# MidDout.net
KiCad netlist of a schematic drawn in Altium Designer
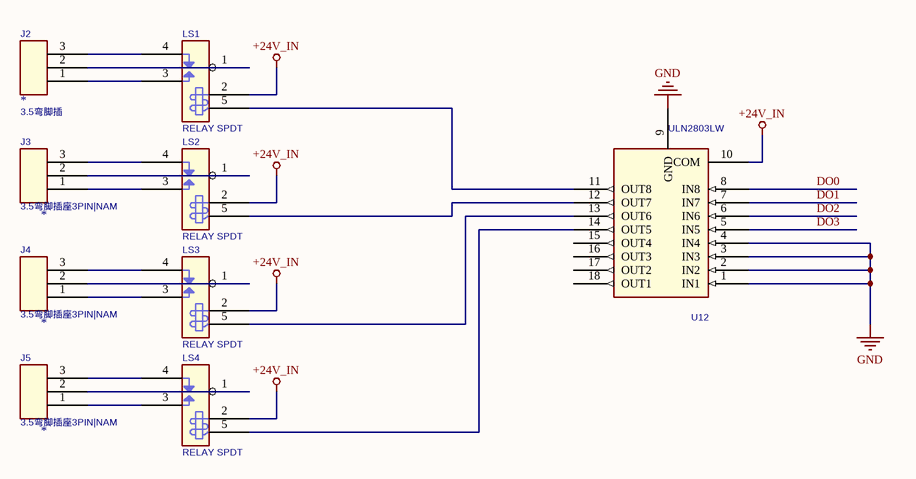
[diagram p0: MidDout.SchDoc]

(export (version "E")
  (design (tool "Eeschema 10.0.6"))
  (components
    (comp (ref "J2")
      (value "*")
      (footprint "3.5-P3")
      (fields (field (name "ALTIUM_UNNAMED_1") "3.5Íä½Å²å"))
      (libsource (lib "*") (part "CON3"))
    )
    (comp (ref "J3")
      (value "*")
      (footprint "3.5-P3")
      (fields (field (name "ALTIUM_UNNAMED_1") "3.5Íä½Å²å×ù3PIN"))
      (libsource (lib "*") (part "CON3"))
    )
    (comp (ref "J4")
      (value "*")
      (footprint "3.5-P3")
      (fields (field (name "ALTIUM_UNNAMED_1") "3.5Íä½Å²å×ù3PIN"))
      (libsource (lib "*") (part "CON3"))
    )
    (comp (ref "J5")
      (value "*")
      (footprint "3.5-P3")
      (fields (field (name "ALTIUM_UNNAMED_1") "3.5Íä½Å²å×ù3PIN"))
      (libsource (lib "*") (part "CON3"))
    )
    (comp (ref "LS1")
      (value "RELAY SPDT")
      (footprint "RELAY_OMRON_G5LE-14")
      (libsource (lib "*") (part "RELAY SPDT_1"))
    )
    (comp (ref "LS2")
      (value "RELAY SPDT")
      (footprint "RELAY_OMRON_G5LE-14")
      (libsource (lib "*") (part "RELAY SPDT_1"))
    )
    (comp (ref "LS3")
      (value "RELAY SPDT")
      (footprint "RELAY_OMRON_G5LE-14")
      (libsource (lib "*") (part "RELAY SPDT_1"))
    )
    (comp (ref "LS4")
      (value "RELAY SPDT")
      (footprint "RELAY_OMRON_G5LE-14")
      (libsource (lib "*") (part "RELAY SPDT_1"))
    )
    (comp (ref "U12") (value "ULN2803LW") (footprint "SO18WN") (libsource (lib "*") (part "ULN2803")))
  )
  (nets
    (net (code "1") (name "+24V_IN") (class "Default")
      (node (ref "LS1") (pin "2") (pinfunction "COIL2_2") (pintype "passive"))
      (node (ref "LS2") (pin "2") (pinfunction "COIL2_2") (pintype "passive"))
      (node (ref "LS3") (pin "2") (pinfunction "COIL2_2") (pintype "passive"))
      (node (ref "LS4") (pin "2") (pinfunction "COIL2_2") (pintype "passive"))
      (node (ref "U12") (pin "10") (pinfunction "COM_10") (pintype "passive"))
    )
    (net (code "2") (name "/DO0") (class "Default")
      (node (ref "U12") (pin "8") (pinfunction "IN8_8") (pintype "input"))
    )
    (net (code "3") (name "/DO1") (class "Default")
      (node (ref "U12") (pin "7") (pinfunction "IN7_7") (pintype "input"))
    )
    (net (code "4") (name "/DO2") (class "Default")
      (node (ref "U12") (pin "6") (pinfunction "IN6_6") (pintype "input"))
    )
    (net (code "5") (name "/DO3") (class "Default")
      (node (ref "U12") (pin "5") (pinfunction "IN5_5") (pintype "input"))
    )
    (net (code "6") (name "GND") (class "Default")
      (node (ref "U12") (pin "1") (pinfunction "IN1_1") (pintype "input"))
      (node (ref "U12") (pin "2") (pinfunction "IN2_2") (pintype "input"))
      (node (ref "U12") (pin "3") (pinfunction "IN3_3") (pintype "input"))
      (node (ref "U12") (pin "4") (pinfunction "IN4_4") (pintype "input"))
      (node (ref "U12") (pin "9") (pinfunction "GND_9") (pintype "power_in"))
    )
    (net (code "7") (name "Net-(LS1-COIL1)") (class "Default")
      (node (ref "LS1") (pin "5") (pinfunction "COIL1_5") (pintype "passive"))
      (node (ref "U12") (pin "11") (pinfunction "OUT8_11") (pintype "output"))
    )
    (net (code "8") (name "Net-(LS1-COMMON)") (class "Default")
      (node (ref "J2") (pin "2") (pinfunction "2_2") (pintype "passive"))
      (node (ref "LS1") (pin "1") (pinfunction "COMMON_1") (pintype "passive"))
    )
    (net (code "9") (name "Net-(LS1-NC)") (class "Default")
      (node (ref "J2") (pin "3") (pinfunction "3_3") (pintype "passive"))
      (node (ref "LS1") (pin "4") (pinfunction "NC_4") (pintype "passive"))
    )
    (net (code "10") (name "Net-(LS1-NO)") (class "Default")
      (node (ref "J2") (pin "1") (pinfunction "1_1") (pintype "passive"))
      (node (ref "LS1") (pin "3") (pinfunction "NO_3") (pintype "passive"))
    )
    (net (code "11") (name "Net-(LS2-COIL1)") (class "Default")
      (node (ref "LS2") (pin "5") (pinfunction "COIL1_5") (pintype "passive"))
      (node (ref "U12") (pin "12") (pinfunction "OUT7_12") (pintype "output"))
    )
    (net (code "12") (name "Net-(LS2-COMMON)") (class "Default")
      (node (ref "J3") (pin "2") (pinfunction "2_2") (pintype "passive"))
      (node (ref "LS2") (pin "1") (pinfunction "COMMON_1") (pintype "passive"))
    )
    (net (code "13") (name "Net-(LS2-NC)") (class "Default")
      (node (ref "J3") (pin "3") (pinfunction "3_3") (pintype "passive"))
      (node (ref "LS2") (pin "4") (pinfunction "NC_4") (pintype "passive"))
    )
    (net (code "14") (name "Net-(LS2-NO)") (class "Default")
      (node (ref "J3") (pin "1") (pinfunction "1_1") (pintype "passive"))
      (node (ref "LS2") (pin "3") (pinfunction "NO_3") (pintype "passive"))
    )
    (net (code "15") (name "Net-(LS3-COIL1)") (class "Default")
      (node (ref "LS3") (pin "5") (pinfunction "COIL1_5") (pintype "passive"))
      (node (ref "U12") (pin "13") (pinfunction "OUT6_13") (pintype "output"))
    )
    (net (code "16") (name "Net-(LS3-COMMON)") (class "Default")
      (node (ref "J4") (pin "2") (pinfunction "2_2") (pintype "passive"))
      (node (ref "LS3") (pin "1") (pinfunction "COMMON_1") (pintype "passive"))
    )
    (net (code "17") (name "Net-(LS3-NC)") (class "Default")
      (node (ref "J4") (pin "3") (pinfunction "3_3") (pintype "passive"))
      (node (ref "LS3") (pin "4") (pinfunction "NC_4") (pintype "passive"))
    )
    (net (code "18") (name "Net-(LS3-NO)") (class "Default")
      (node (ref "J4") (pin "1") (pinfunction "1_1") (pintype "passive"))
      (node (ref "LS3") (pin "3") (pinfunction "NO_3") (pintype "passive"))
    )
    (net (code "19") (name "Net-(LS4-COIL1)") (class "Default")
      (node (ref "LS4") (pin "5") (pinfunction "COIL1_5") (pintype "passive"))
      (node (ref "U12") (pin "14") (pinfunction "OUT5_14") (pintype "output"))
    )
    (net (code "20") (name "Net-(LS4-COMMON)") (class "Default")
      (node (ref "J5") (pin "2") (pinfunction "2_2") (pintype "passive"))
      (node (ref "LS4") (pin "1") (pinfunction "COMMON_1") (pintype "passive"))
    )
    (net (code "21") (name "Net-(LS4-NC)") (class "Default")
      (node (ref "J5") (pin "3") (pinfunction "3_3") (pintype "passive"))
      (node (ref "LS4") (pin "4") (pinfunction "NC_4") (pintype "passive"))
    )
    (net (code "22") (name "Net-(LS4-NO)") (class "Default")
      (node (ref "J5") (pin "1") (pinfunction "1_1") (pintype "passive"))
      (node (ref "LS4") (pin "3") (pinfunction "NO_3") (pintype "passive"))
    )
    (net (code "23") (name "unconnected-(U12-OUT1-Pad18)") (class "Default")
      (node (ref "U12") (pin "18") (pinfunction "OUT1_18") (pintype "output"))
    )
    (net (code "24") (name "unconnected-(U12-OUT2-Pad17)") (class "Default")
      (node (ref "U12") (pin "17") (pinfunction "OUT2_17") (pintype "output"))
    )
    (net (code "25") (name "unconnected-(U12-OUT3-Pad16)") (class "Default")
      (node (ref "U12") (pin "16") (pinfunction "OUT3_16") (pintype "output"))
    )
    (net (code "26") (name "unconnected-(U12-OUT4-Pad15)") (class "Default")
      (node (ref "U12") (pin "15") (pinfunction "OUT4_15") (pintype "output"))
    )
  )
)
